# HalfBridge.net
KiCad netlist of a schematic drawn in Altium Designer
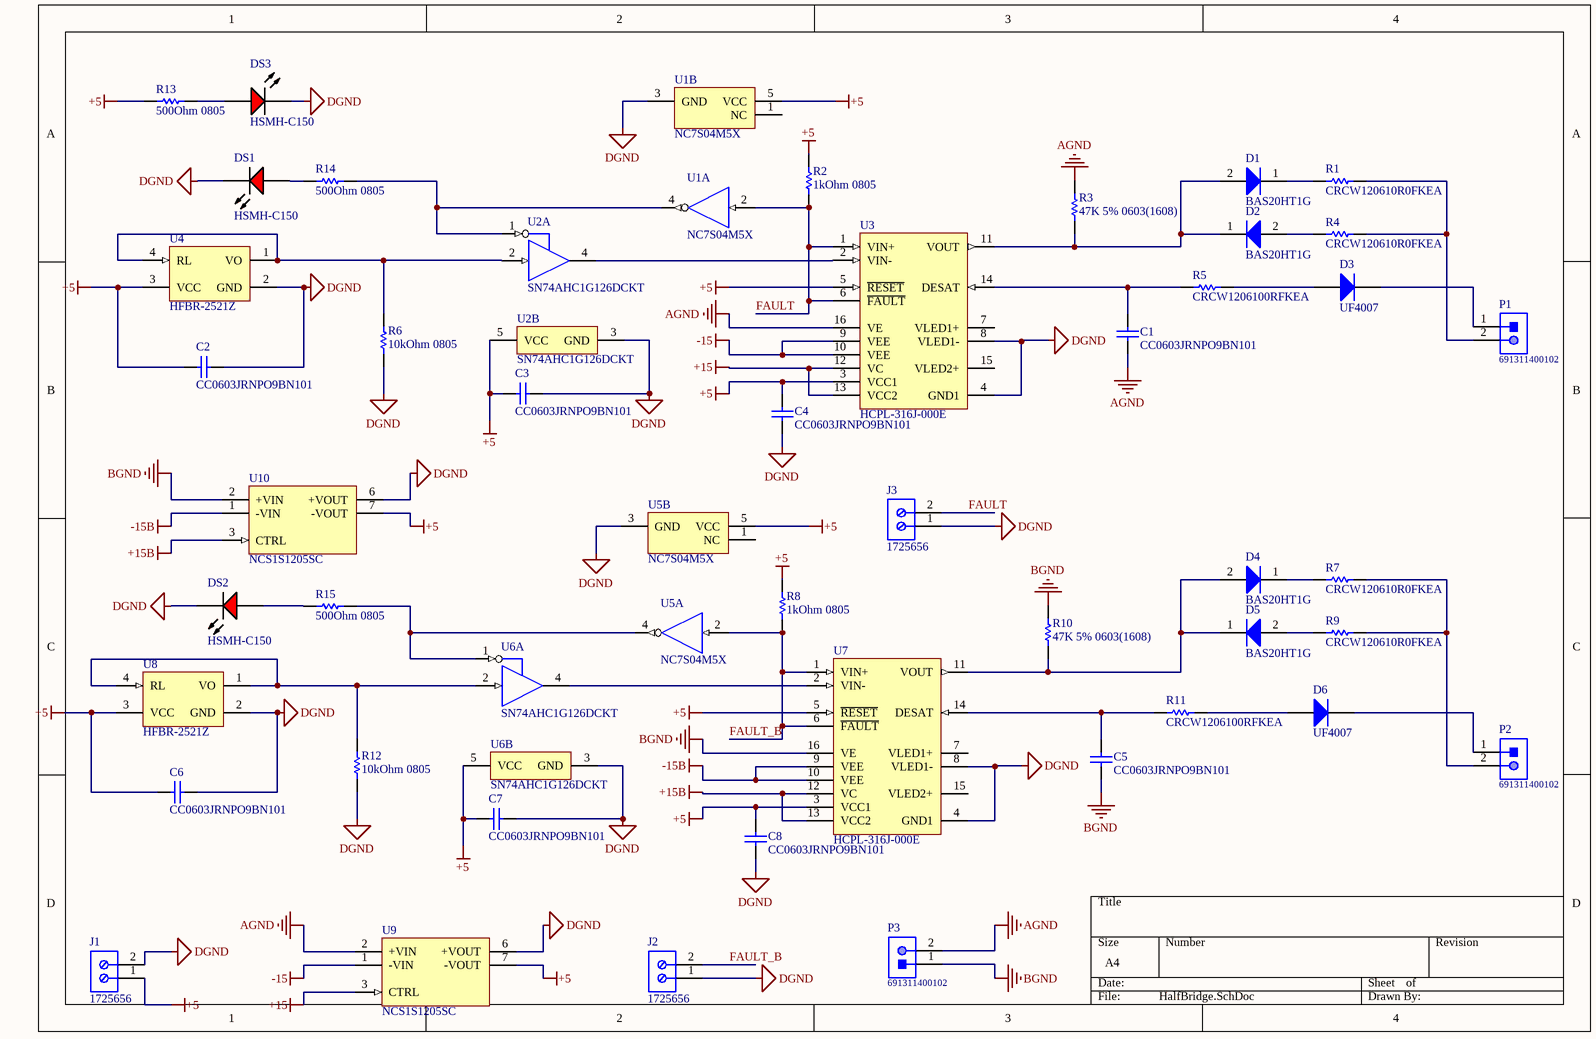
[diagram p0: HalfBridge.SchDoc]

(export (version "E")
  (design (tool "Eeschema 10.0.6"))
  (components
    (comp (ref "C1")
      (value "CC0603JRNPO9BN101")
      (footprint "CAPC1608X90X40ML10T20")
      (description "Chip Capacitor, 100 pF, +/- 5%, 50 V, -55 to 125 degC, 0603 (1608 Metric), RoHS, Tape and Reel")
      (fields (field (name "TOLERANCE") "5%") (field (name "VOLTAGE") "50V"))
      (libsource (lib "Altium Content Vault") (part "CAP-NP-2"))
    )
    (comp (ref "C2")
      (value "CC0603JRNPO9BN101")
      (footprint "CAPC1608X90X40ML10T20")
      (description "Chip Capacitor, 100 pF, +/- 5%, 50 V, -55 to 125 degC, 0603 (1608 Metric), RoHS, Tape and Reel")
      (fields (field (name "TOLERANCE") "5%") (field (name "VOLTAGE") "50V"))
      (libsource (lib "Altium Content Vault") (part "CAP-NP-2"))
    )
    (comp (ref "C3")
      (value "CC0603JRNPO9BN101")
      (footprint "CAPC1608X90X40ML10T20")
      (description "Chip Capacitor, 100 pF, +/- 5%, 50 V, -55 to 125 degC, 0603 (1608 Metric), RoHS, Tape and Reel")
      (fields (field (name "TOLERANCE") "5%") (field (name "VOLTAGE") "50V"))
      (libsource (lib "Altium Content Vault") (part "CAP-NP-2"))
    )
    (comp (ref "C4")
      (value "CC0603JRNPO9BN101")
      (footprint "CAPC1608X90X40ML10T20")
      (description "Chip Capacitor, 100 pF, +/- 5%, 50 V, -55 to 125 degC, 0603 (1608 Metric), RoHS, Tape and Reel")
      (fields (field (name "TOLERANCE") "5%") (field (name "VOLTAGE") "50V"))
      (libsource (lib "Altium Content Vault") (part "CAP-NP-2"))
    )
    (comp (ref "C5")
      (value "CC0603JRNPO9BN101")
      (footprint "CAPC1608X90X40ML10T20")
      (description "Chip Capacitor, 100 pF, +/- 5%, 50 V, -55 to 125 degC, 0603 (1608 Metric), RoHS, Tape and Reel")
      (fields (field (name "TOLERANCE") "5%") (field (name "VOLTAGE") "50V"))
      (libsource (lib "Altium Content Vault") (part "CAP-NP-2"))
    )
    (comp (ref "C6")
      (value "CC0603JRNPO9BN101")
      (footprint "CAPC1608X90X40ML10T20")
      (description "Chip Capacitor, 100 pF, +/- 5%, 50 V, -55 to 125 degC, 0603 (1608 Metric), RoHS, Tape and Reel")
      (fields (field (name "TOLERANCE") "5%") (field (name "VOLTAGE") "50V"))
      (libsource (lib "Altium Content Vault") (part "CAP-NP-2"))
    )
    (comp (ref "C7")
      (value "CC0603JRNPO9BN101")
      (footprint "CAPC1608X90X40ML10T20")
      (description "Chip Capacitor, 100 pF, +/- 5%, 50 V, -55 to 125 degC, 0603 (1608 Metric), RoHS, Tape and Reel")
      (fields (field (name "TOLERANCE") "5%") (field (name "VOLTAGE") "50V"))
      (libsource (lib "Altium Content Vault") (part "CAP-NP-2"))
    )
    (comp (ref "C8")
      (value "CC0603JRNPO9BN101")
      (footprint "CAPC1608X90X40ML10T20")
      (description "Chip Capacitor, 100 pF, +/- 5%, 50 V, -55 to 125 degC, 0603 (1608 Metric), RoHS, Tape and Reel")
      (fields (field (name "TOLERANCE") "5%") (field (name "VOLTAGE") "50V"))
      (libsource (lib "Altium Content Vault") (part "CAP-NP-2"))
    )
    (comp (ref "D1")
      (value "BAS20HT1G")
      (footprint "ONSC-SOD-323-2-477-02_V")
      (description "High Voltage Switching Diode, 2-Pin SOD-323, Pb-Free, Tape and Reel")
      (fields (field (name "MANUFACTURER") "On Semiconductor"))
      (libsource (lib "Altium Content Vault") (part "ONSC-D-K1A2-2"))
    )
    (comp (ref "D2")
      (value "BAS20HT1G")
      (footprint "ONSC-SOD-323-2-477-02_V")
      (description "High Voltage Switching Diode, 2-Pin SOD-323, Pb-Free, Tape and Reel")
      (fields (field (name "MANUFACTURER") "On Semiconductor"))
      (libsource (lib "Altium Content Vault") (part "ONSC-D-K1A2-2"))
    )
    (comp (ref "D3")
      (value "UF4007")
      (footprint "FAIR-DO-41-2")
      (description "Fast Rectufuer, 2.08 W, 2-Pin DO-41, RoHS, Tape and Reel")
      (fields (field (name "MANUFACTURER") "Fairchild"))
      (libsource (lib "Altium Content Vault") (part "D-AK-2"))
    )
    (comp (ref "D4")
      (value "BAS20HT1G")
      (footprint "ONSC-SOD-323-2-477-02_V")
      (description "High Voltage Switching Diode, 2-Pin SOD-323, Pb-Free, Tape and Reel")
      (fields (field (name "MANUFACTURER") "On Semiconductor"))
      (libsource (lib "Altium Content Vault") (part "ONSC-D-K1A2-2"))
    )
    (comp (ref "D5")
      (value "BAS20HT1G")
      (footprint "ONSC-SOD-323-2-477-02_V")
      (description "High Voltage Switching Diode, 2-Pin SOD-323, Pb-Free, Tape and Reel")
      (fields (field (name "MANUFACTURER") "On Semiconductor"))
      (libsource (lib "Altium Content Vault") (part "ONSC-D-K1A2-2"))
    )
    (comp (ref "D6")
      (value "UF4007")
      (footprint "FAIR-DO-41-2")
      (description "Fast Rectufuer, 2.08 W, 2-Pin DO-41, RoHS, Tape and Reel")
      (fields (field (name "MANUFACTURER") "Fairchild"))
      (libsource (lib "Altium Content Vault") (part "D-AK-2"))
    )
    (comp (ref "DS1")
      (value "HSMH-C150")
      (footprint "AVAG-HSMX-C150_V")
      (description "LED Uni-Color Red, 65 mW, 25 mA, -40 to 85 degC, 2-Pin SMD, RoHS, Tape and Reel")
      (fields (field (name "MANUFACTURER") "Avago"))
      (libsource (lib "Altium Content Vault") (part "LED-RED-AK-2"))
    )
    (comp (ref "DS2")
      (value "HSMH-C150")
      (footprint "AVAG-HSMX-C150_V")
      (description "LED Uni-Color Red, 65 mW, 25 mA, -40 to 85 degC, 2-Pin SMD, RoHS, Tape and Reel")
      (fields (field (name "MANUFACTURER") "Avago"))
      (libsource (lib "Altium Content Vault") (part "LED-RED-AK-2"))
    )
    (comp (ref "DS3")
      (value "HSMH-C150")
      (footprint "AVAG-HSMX-C150_V")
      (description "LED Uni-Color Red, 65 mW, 25 mA, -40 to 85 degC, 2-Pin SMD, RoHS, Tape and Reel")
      (fields (field (name "MANUFACTURER") "Avago"))
      (libsource (lib "Altium Content Vault") (part "LED-RED-AK-2"))
    )
    (comp (ref "J1")
      (value "1725656")
      (footprint "PHOE-1725656-2")
      (description "Male Header, Pitch 2.54 mm, 1 x 2 Position, Height 9 mm, Tail Length 3.5 mm")
      (fields (field (name "MANUFACTURER") "Phoenix Contact"))
      (libsource (lib "Altium Content Vault") (part "CN-1P-F-TB2"))
    )
    (comp (ref "J2")
      (value "1725656")
      (footprint "PHOE-1725656-2")
      (description "Male Header, Pitch 2.54 mm, 1 x 2 Position, Height 9 mm, Tail Length 3.5 mm")
      (fields (field (name "MANUFACTURER") "Phoenix Contact"))
      (libsource (lib "Altium Content Vault") (part "CN-1P-F-TB2"))
    )
    (comp (ref "J3")
      (value "1725656")
      (footprint "PHOE-1725656-2")
      (description "Male Header, Pitch 2.54 mm, 1 x 2 Position, Height 9 mm, Tail Length 3.5 mm")
      (fields (field (name "MANUFACTURER") "Phoenix Contact"))
      (libsource (lib "Altium Content Vault") (part "CN-1P-F-TB2"))
    )
    (comp (ref "P1")
      (value "691311400102")
      (footprint "691311400102")
      (description "Serie 3114 - 7.62mm Close Vertical PCB Header WR-TBL, 2 pin")
      (fields (field (name "MANUFACTURER") "Wurth Elektronik") (field (name "PUBLISHER") "WurthElektronik"))
      (libsource (lib "Altium Content Vault") (part "WE-CN-1P-M-R2"))
    )
    (comp (ref "P2")
      (value "691311400102")
      (footprint "691311400102")
      (description "Serie 3114 - 7.62mm Close Vertical PCB Header WR-TBL, 2 pin")
      (fields (field (name "MANUFACTURER") "Wurth Elektronik") (field (name "PUBLISHER") "WurthElektronik"))
      (libsource (lib "Altium Content Vault") (part "WE-CN-1P-M-R2"))
    )
    (comp (ref "P3")
      (value "691311400102")
      (footprint "691311400102")
      (description "Serie 3114 - 7.62mm Close Vertical PCB Header WR-TBL, 2 pin")
      (fields (field (name "MANUFACTURER") "Wurth Elektronik") (field (name "PUBLISHER") "WurthElektronik"))
      (libsource (lib "") (part "WE-CN-1P-M-R2_1"))
    )
    (comp (ref "R1")
      (value "CRCW120610R0FKEA")
      (footprint "RESC3216X60X45ML10T20")
      (fields (field (name "MANUFACTURER") "Vishay Dale"))
      (libsource (lib "Altium Content Vault") (part "RES"))
    )
    (comp (ref "R2")
      (value "1kOhm 0805")
      (footprint "RESC2013X50X30LL20T20")
      (fields (field (name "MANUFACTURER") "Vishay Dale") (field (name "PART NUMBER") "CRCW08050000Z0EA"))
      (libsource (lib "Altium Content Vault") (part "RES"))
    )
    (comp (ref "R3")
      (value "47K 5% 0603(1608)")
      (footprint "RESC0603(1608)_L")
      (description "47K 0.1W 5% 0603 (1608 Metric)  SMD")
      (fields (field (name "TOLERANCE") "5 %") (field (name "POWER") "0.1 W"))
      (libsource (lib "Altium Content Vault") (part "RES"))
    )
    (comp (ref "R4")
      (value "CRCW120610R0FKEA")
      (footprint "RESC3216X60X45ML10T20")
      (fields (field (name "MANUFACTURER") "Vishay Dale"))
      (libsource (lib "Altium Content Vault") (part "RES"))
    )
    (comp (ref "R5")
      (value "CRCW1206100RFKEA")
      (footprint "RESC3216X60X45ML10T20")
      (fields (field (name "MANUFACTURER") "Vishay Dale"))
      (libsource (lib "Altium Content Vault") (part "RES"))
    )
    (comp (ref "R6")
      (value "10kOhm 0805")
      (footprint "RESC2013X50X30LL20T20")
      (fields (field (name "MANUFACTURER") "Vishay Dale") (field (name "PART NUMBER") "CRCW08050000Z0EA"))
      (libsource (lib "Altium Content Vault") (part "RES"))
    )
    (comp (ref "R7")
      (value "CRCW120610R0FKEA")
      (footprint "RESC3216X60X45ML10T20")
      (fields (field (name "MANUFACTURER") "Vishay Dale"))
      (libsource (lib "Altium Content Vault") (part "RES"))
    )
    (comp (ref "R8")
      (value "1kOhm 0805")
      (footprint "RESC2013X50X30LL20T20")
      (fields (field (name "MANUFACTURER") "Vishay Dale") (field (name "PART NUMBER") "CRCW08050000Z0EA"))
      (libsource (lib "Altium Content Vault") (part "RES"))
    )
    (comp (ref "R9")
      (value "CRCW120610R0FKEA")
      (footprint "RESC3216X60X45ML10T20")
      (fields (field (name "MANUFACTURER") "Vishay Dale"))
      (libsource (lib "Altium Content Vault") (part "RES"))
    )
    (comp (ref "R10")
      (value "47K 5% 0603(1608)")
      (footprint "RESC0603(1608)_L")
      (description "47K 0.1W 5% 0603 (1608 Metric)  SMD")
      (fields (field (name "TOLERANCE") "5 %") (field (name "POWER") "0.1 W"))
      (libsource (lib "Altium Content Vault") (part "RES"))
    )
    (comp (ref "R11")
      (value "CRCW1206100RFKEA")
      (footprint "RESC3216X60X45ML10T20")
      (fields (field (name "MANUFACTURER") "Vishay Dale"))
      (libsource (lib "Altium Content Vault") (part "RES"))
    )
    (comp (ref "R12")
      (value "10kOhm 0805")
      (footprint "RESC2013X50X30LL20T20")
      (fields (field (name "MANUFACTURER") "Vishay Dale") (field (name "PART NUMBER") "CRCW08050000Z0EA"))
      (libsource (lib "Altium Content Vault") (part "RES"))
    )
    (comp (ref "R13")
      (value "500Ohm 0805")
      (footprint "RESC2013X50X30LL20T20")
      (fields (field (name "MANUFACTURER") "Vishay Dale") (field (name "PART NUMBER") "CRCW08050000Z0EA"))
      (libsource (lib "Altium Content Vault") (part "RES"))
    )
    (comp (ref "R14")
      (value "500Ohm 0805")
      (footprint "RESC2013X50X30LL20T20")
      (fields (field (name "MANUFACTURER") "Vishay Dale") (field (name "PART NUMBER") "CRCW08050000Z0EA"))
      (libsource (lib "Altium Content Vault") (part "RES"))
    )
    (comp (ref "R15")
      (value "500Ohm 0805")
      (footprint "RESC2013X50X30LL20T20")
      (fields (field (name "MANUFACTURER") "Vishay Dale") (field (name "PART NUMBER") "CRCW08050000Z0EA"))
      (libsource (lib "Altium Content Vault") (part "RES"))
    )
    (comp (ref "U1")
      (value "NC7S04M5X")
      (footprint "FAIR-SOT23-5_V")
      (description "TinyLogic(R) HS Inverter, 2.6 mA, 2 to 6 V, -40 to 85 degC, 5-Pin SOT23, RoHS, Tape and Reel")
      (fields (field (name "MANUFACTURER") "Fairchild Semiconductor"))
      (libsource (lib "Altium Content Vault") (part "FAIR-NC7SX04-5"))
    )
    (comp (ref "U2")
      (value "SN74AHC1G126DCKT")
      (footprint "DCK0005A_N")
      (description "Single Bus Buffer Gate With 3-State Outputs, DCK0005A, SMALL T&R")
      (fields
        (field (name "MANUFACTURER") "Texas Instruments")
        (field (name "GENERIC PART NUMBER") "SN74AHC1G126")
      )
      (libsource (lib "Altium Content Vault") (part "TI-SN74XXXXXX126-5"))
    )
    (comp (ref "U3")
      (value "HCPL-316J-000E")
      (footprint "AVAG-SOIC-16_V")
      (fields (field (name "MANUFACTURER") "AvagoTechnologies"))
      (libsource (lib "Altium Content Vault") (part "AVAG-HCPL-316J-SOIC-16"))
    )
    (comp (ref "U4")
      (value "HFBR-2521Z")
      (footprint "BCM-HFBR-2521Z-4")
      (description "The Versatile Fiber Optic Connection, 5 MBd, -40 to 85 degC, 4-Pin, RoHS, Rail/Tube")
      (fields (field (name "MANUFACTURER") "Broadcom"))
      (libsource (lib "Altium Content Vault") (part "BCM-HFBR-2521Z-4"))
    )
    (comp (ref "U5")
      (value "NC7S04M5X")
      (footprint "FAIR-SOT23-5_V")
      (description "TinyLogic(R) HS Inverter, 2.6 mA, 2 to 6 V, -40 to 85 degC, 5-Pin SOT23, RoHS, Tape and Reel")
      (fields (field (name "MANUFACTURER") "Fairchild Semiconductor"))
      (libsource (lib "Altium Content Vault") (part "FAIR-NC7SX04-5"))
    )
    (comp (ref "U6")
      (value "SN74AHC1G126DCKT")
      (footprint "DCK0005A_N")
      (description "Single Bus Buffer Gate With 3-State Outputs, DCK0005A, SMALL T&R")
      (fields
        (field (name "MANUFACTURER") "Texas Instruments")
        (field (name "GENERIC PART NUMBER") "SN74AHC1G126")
      )
      (libsource (lib "Altium Content Vault") (part "TI-SN74XXXXXX126-5"))
    )
    (comp (ref "U7")
      (value "HCPL-316J-000E")
      (footprint "AVAG-SOIC-16_V")
      (fields (field (name "MANUFACTURER") "AvagoTechnologies"))
      (libsource (lib "Altium Content Vault") (part "AVAG-HCPL-316J-SOIC-16"))
    )
    (comp (ref "U8")
      (value "HFBR-2521Z")
      (footprint "BCM-HFBR-2521Z-4")
      (description "The Versatile Fiber Optic Connection, 5 MBd, -40 to 85 degC, 4-Pin, RoHS, Rail/Tube")
      (fields (field (name "MANUFACTURER") "Broadcom"))
      (libsource (lib "Altium Content Vault") (part "BCM-HFBR-2521Z-4"))
    )
    (comp (ref "U9")
      (value "NCS1S1205SC")
      (footprint "MURA-NCS1S1205SC-5_V")
      (fields (field (name "GENERIC PART NUMBER") "NCS1"))
      (libsource (lib "Altium Content Vault") (part "MURA-NCS1S1205SC-5"))
    )
    (comp (ref "U10")
      (value "NCS1S1205SC")
      (footprint "MURA-NCS1S1205SC-5_V")
      (fields (field (name "GENERIC PART NUMBER") "NCS1"))
      (libsource (lib "Altium Content Vault") (part "MURA-NCS1S1205SC-5"))
    )
  )
  (nets
    (net (code "1") (name "+5") (class "Default")
      (node (ref "C2") (pin "1") (pinfunction "1_1") (pintype "passive"))
      (node (ref "C3") (pin "1") (pinfunction "1_1") (pintype "passive"))
      (node (ref "C4") (pin "1") (pinfunction "1_1") (pintype "passive"))
      (node (ref "C6") (pin "1") (pinfunction "1_1") (pintype "passive"))
      (node (ref "C7") (pin "1") (pinfunction "1_1") (pintype "passive"))
      (node (ref "C8") (pin "1") (pinfunction "1_1") (pintype "passive"))
      (node (ref "J1") (pin "1") (pinfunction "1_1") (pintype "passive"))
      (node (ref "R13") (pin "2") (pinfunction "2_2") (pintype "passive"))
      (node (ref "R2") (pin "2") (pinfunction "2_2") (pintype "passive"))
      (node (ref "R8") (pin "2") (pinfunction "2_2") (pintype "passive"))
      (node (ref "U1") (pin "5") (pinfunction "VCC_5") (pintype "power_in"))
      (node (ref "U10") (pin "7") (pinfunction "-VOUT_7") (pintype "power_in"))
      (node (ref "U2") (pin "5") (pinfunction "VCC_5") (pintype "power_in"))
      (node (ref "U3") (pin "3") (pinfunction "VCC1_3") (pintype "power_in"))
      (node (ref "U3") (pin "5") (pinfunction "~{RESET}_5") (pintype "input"))
      (node (ref "U4") (pin "3") (pinfunction "VCC_3") (pintype "power_in"))
      (node (ref "U5") (pin "5") (pinfunction "VCC_5") (pintype "power_in"))
      (node (ref "U6") (pin "5") (pinfunction "VCC_5") (pintype "power_in"))
      (node (ref "U7") (pin "3") (pinfunction "VCC1_3") (pintype "power_in"))
      (node (ref "U7") (pin "5") (pinfunction "~{RESET}_5") (pintype "input"))
      (node (ref "U8") (pin "3") (pinfunction "VCC_3") (pintype "power_in"))
      (node (ref "U9") (pin "7") (pinfunction "-VOUT_7") (pintype "power_in"))
    )
    (net (code "2") (name "+15") (class "Default")
      (node (ref "U3") (pin "12") (pinfunction "VC_12") (pintype "power_in"))
      (node (ref "U3") (pin "13") (pinfunction "VCC2_13") (pintype "power_in"))
      (node (ref "U9") (pin "3") (pinfunction "CTRL_3") (pintype "input"))
    )
    (net (code "3") (name "+15B") (class "Default")
      (node (ref "U10") (pin "3") (pinfunction "CTRL_3") (pintype "input"))
      (node (ref "U7") (pin "12") (pinfunction "VC_12") (pintype "power_in"))
      (node (ref "U7") (pin "13") (pinfunction "VCC2_13") (pintype "power_in"))
    )
    (net (code "4") (name "-15") (class "Default")
      (node (ref "U3") (pin "10") (pinfunction "VEE_10") (pintype "power_in"))
      (node (ref "U3") (pin "9") (pinfunction "VEE_9") (pintype "power_in"))
      (node (ref "U9") (pin "1") (pinfunction "-VIN_1") (pintype "power_in"))
    )
    (net (code "5") (name "-15B") (class "Default")
      (node (ref "U10") (pin "1") (pinfunction "-VIN_1") (pintype "power_in"))
      (node (ref "U7") (pin "10") (pinfunction "VEE_10") (pintype "power_in"))
      (node (ref "U7") (pin "9") (pinfunction "VEE_9") (pintype "power_in"))
    )
    (net (code "6") (name "/FAULT") (class "Default")
      (node (ref "J3") (pin "2") (pinfunction "2_2") (pintype "passive"))
      (node (ref "R2") (pin "1") (pinfunction "1_1") (pintype "passive"))
      (node (ref "U1") (pin "2") (pinfunction "A_2") (pintype "input"))
      (node (ref "U3") (pin "1") (pinfunction "VIN+_1") (pintype "input"))
      (node (ref "U3") (pin "6") (pinfunction "~{FAULT}_6") (pintype "tri_state"))
    )
    (net (code "7") (name "/FAULT_B") (class "Default")
      (node (ref "J2") (pin "2") (pinfunction "2_2") (pintype "passive"))
      (node (ref "R8") (pin "1") (pinfunction "1_1") (pintype "passive"))
      (node (ref "U5") (pin "2") (pinfunction "A_2") (pintype "input"))
      (node (ref "U7") (pin "1") (pinfunction "VIN+_1") (pintype "input"))
      (node (ref "U7") (pin "6") (pinfunction "~{FAULT}_6") (pintype "tri_state"))
    )
    (net (code "8") (name "AGND") (class "Default")
      (node (ref "C1") (pin "2") (pinfunction "2_2") (pintype "passive"))
      (node (ref "P3") (pin "2") (pinfunction "2_2") (pintype "passive"))
      (node (ref "R3") (pin "2") (pinfunction "2_2") (pintype "passive"))
      (node (ref "U3") (pin "16") (pinfunction "VE_16") (pintype "power_in"))
      (node (ref "U9") (pin "2") (pinfunction "+VIN_2") (pintype "power_in"))
    )
    (net (code "9") (name "BGND") (class "Default")
      (node (ref "C5") (pin "2") (pinfunction "2_2") (pintype "passive"))
      (node (ref "P3") (pin "1") (pinfunction "1_1") (pintype "passive"))
      (node (ref "R10") (pin "2") (pinfunction "2_2") (pintype "passive"))
      (node (ref "U10") (pin "2") (pinfunction "+VIN_2") (pintype "power_in"))
      (node (ref "U7") (pin "16") (pinfunction "VE_16") (pintype "power_in"))
    )
    (net (code "10") (name "DGND") (class "Default")
      (node (ref "C2") (pin "2") (pinfunction "2_2") (pintype "passive"))
      (node (ref "C3") (pin "2") (pinfunction "2_2") (pintype "passive"))
      (node (ref "C4") (pin "2") (pinfunction "2_2") (pintype "passive"))
      (node (ref "C6") (pin "2") (pinfunction "2_2") (pintype "passive"))
      (node (ref "C7") (pin "2") (pinfunction "2_2") (pintype "passive"))
      (node (ref "C8") (pin "2") (pinfunction "2_2") (pintype "passive"))
      (node (ref "DS1") (pin "2") (pinfunction "K_2") (pintype "passive"))
      (node (ref "DS2") (pin "2") (pinfunction "K_2") (pintype "passive"))
      (node (ref "DS3") (pin "2") (pinfunction "K_2") (pintype "passive"))
      (node (ref "J1") (pin "2") (pinfunction "2_2") (pintype "passive"))
      (node (ref "J2") (pin "1") (pinfunction "1_1") (pintype "passive"))
      (node (ref "J3") (pin "1") (pinfunction "1_1") (pintype "passive"))
      (node (ref "R12") (pin "1") (pinfunction "1_1") (pintype "passive"))
      (node (ref "R6") (pin "1") (pinfunction "1_1") (pintype "passive"))
      (node (ref "U1") (pin "3") (pinfunction "GND_3") (pintype "power_in"))
      (node (ref "U10") (pin "6") (pinfunction "+VOUT_6") (pintype "power_in"))
      (node (ref "U2") (pin "3") (pinfunction "GND_3") (pintype "power_in"))
      (node (ref "U3") (pin "4") (pinfunction "GND1_4") (pintype "power_in"))
      (node (ref "U3") (pin "8") (pinfunction "VLED1-_8") (pintype "passive"))
      (node (ref "U4") (pin "2") (pinfunction "GND_2") (pintype "power_in"))
      (node (ref "U5") (pin "3") (pinfunction "GND_3") (pintype "power_in"))
      (node (ref "U6") (pin "3") (pinfunction "GND_3") (pintype "power_in"))
      (node (ref "U7") (pin "4") (pinfunction "GND1_4") (pintype "power_in"))
      (node (ref "U7") (pin "8") (pinfunction "VLED1-_8") (pintype "passive"))
      (node (ref "U8") (pin "2") (pinfunction "GND_2") (pintype "power_in"))
      (node (ref "U9") (pin "6") (pinfunction "+VOUT_6") (pintype "power_in"))
    )
    (net (code "11") (name "Net-(D1-A)") (class "Default")
      (node (ref "D1") (pin "2") (pinfunction "A_2") (pintype "passive"))
      (node (ref "D2") (pin "1") (pinfunction "K_1") (pintype "passive"))
      (node (ref "R3") (pin "1") (pinfunction "1_1") (pintype "passive"))
      (node (ref "U3") (pin "11") (pinfunction "VOUT_11") (pintype "output"))
    )
    (net (code "12") (name "Net-(D1-K)") (class "Default")
      (node (ref "D1") (pin "1") (pinfunction "K_1") (pintype "passive"))
      (node (ref "R1") (pin "1") (pinfunction "1_1") (pintype "passive"))
    )
    (net (code "13") (name "Net-(D2-A)") (class "Default")
      (node (ref "D2") (pin "2") (pinfunction "A_2") (pintype "passive"))
      (node (ref "R4") (pin "1") (pinfunction "1_1") (pintype "passive"))
    )
    (net (code "14") (name "Net-(D3-A)") (class "Default")
      (node (ref "D3") (pin "1") (pinfunction "A_1") (pintype "passive"))
      (node (ref "R5") (pin "2") (pinfunction "2_2") (pintype "passive"))
    )
    (net (code "15") (name "Net-(D3-K)") (class "Default")
      (node (ref "D3") (pin "2") (pinfunction "K_2") (pintype "passive"))
      (node (ref "P1") (pin "1") (pinfunction "1_1") (pintype "passive"))
    )
    (net (code "16") (name "Net-(D4-A)") (class "Default")
      (node (ref "D4") (pin "2") (pinfunction "A_2") (pintype "passive"))
      (node (ref "D5") (pin "1") (pinfunction "K_1") (pintype "passive"))
      (node (ref "R10") (pin "1") (pinfunction "1_1") (pintype "passive"))
      (node (ref "U7") (pin "11") (pinfunction "VOUT_11") (pintype "output"))
    )
    (net (code "17") (name "Net-(D4-K)") (class "Default")
      (node (ref "D4") (pin "1") (pinfunction "K_1") (pintype "passive"))
      (node (ref "R7") (pin "1") (pinfunction "1_1") (pintype "passive"))
    )
    (net (code "18") (name "Net-(D5-A)") (class "Default")
      (node (ref "D5") (pin "2") (pinfunction "A_2") (pintype "passive"))
      (node (ref "R9") (pin "1") (pinfunction "1_1") (pintype "passive"))
    )
    (net (code "19") (name "Net-(D6-A)") (class "Default")
      (node (ref "D6") (pin "1") (pinfunction "A_1") (pintype "passive"))
      (node (ref "R11") (pin "2") (pinfunction "2_2") (pintype "passive"))
    )
    (net (code "20") (name "Net-(D6-K)") (class "Default")
      (node (ref "D6") (pin "2") (pinfunction "K_2") (pintype "passive"))
      (node (ref "P2") (pin "1") (pinfunction "1_1") (pintype "passive"))
    )
    (net (code "21") (name "Net-(DS1-A)") (class "Default")
      (node (ref "DS1") (pin "1") (pinfunction "A_1") (pintype "passive"))
      (node (ref "R14") (pin "2") (pinfunction "2_2") (pintype "passive"))
    )
    (net (code "22") (name "Net-(DS2-A)") (class "Default")
      (node (ref "DS2") (pin "1") (pinfunction "A_1") (pintype "passive"))
      (node (ref "R15") (pin "2") (pinfunction "2_2") (pintype "passive"))
    )
    (net (code "23") (name "Net-(DS3-A)") (class "Default")
      (node (ref "DS3") (pin "1") (pinfunction "A_1") (pintype "passive"))
      (node (ref "R13") (pin "1") (pinfunction "1_1") (pintype "passive"))
    )
    (net (code "24") (name "Net-(P1-Pad2)") (class "Default")
      (node (ref "P1") (pin "2") (pinfunction "2_2") (pintype "passive"))
      (node (ref "R1") (pin "2") (pinfunction "2_2") (pintype "passive"))
      (node (ref "R4") (pin "2") (pinfunction "2_2") (pintype "passive"))
    )
    (net (code "25") (name "Net-(P2-Pad2)") (class "Default")
      (node (ref "P2") (pin "2") (pinfunction "2_2") (pintype "passive"))
      (node (ref "R7") (pin "2") (pinfunction "2_2") (pintype "passive"))
      (node (ref "R9") (pin "2") (pinfunction "2_2") (pintype "passive"))
    )
    (net (code "26") (name "Net-(U1A-Y)") (class "Default")
      (node (ref "R14") (pin "1") (pinfunction "1_1") (pintype "passive"))
      (node (ref "U1") (pin "4") (pinfunction "Y_4") (pintype "output"))
      (node (ref "U2") (pin "1") (pinfunction "OE_1") (pintype "input"))
    )
    (net (code "27") (name "Net-(U2A-A)") (class "Default")
      (node (ref "R6") (pin "2") (pinfunction "2_2") (pintype "passive"))
      (node (ref "U2") (pin "2") (pinfunction "A_2") (pintype "input"))
      (node (ref "U4") (pin "1") (pinfunction "VO_1") (pintype "power_in"))
      (node (ref "U4") (pin "4") (pinfunction "RL_4") (pintype "input"))
    )
    (net (code "28") (name "Net-(U2A-Y)") (class "Default")
      (node (ref "U2") (pin "4") (pinfunction "Y_4") (pintype "tri_state"))
      (node (ref "U3") (pin "2") (pinfunction "VIN-_2") (pintype "input"))
    )
    (net (code "29") (name "Net-(U3-DESAT)") (class "Default")
      (node (ref "C1") (pin "1") (pinfunction "1_1") (pintype "passive"))
      (node (ref "R5") (pin "1") (pinfunction "1_1") (pintype "passive"))
      (node (ref "U3") (pin "14") (pinfunction "DESAT_14") (pintype "input"))
    )
    (net (code "30") (name "Net-(U5A-Y)") (class "Default")
      (node (ref "R15") (pin "1") (pinfunction "1_1") (pintype "passive"))
      (node (ref "U5") (pin "4") (pinfunction "Y_4") (pintype "output"))
      (node (ref "U6") (pin "1") (pinfunction "OE_1") (pintype "input"))
    )
    (net (code "31") (name "Net-(U6A-A)") (class "Default")
      (node (ref "R12") (pin "2") (pinfunction "2_2") (pintype "passive"))
      (node (ref "U6") (pin "2") (pinfunction "A_2") (pintype "input"))
      (node (ref "U8") (pin "1") (pinfunction "VO_1") (pintype "power_in"))
      (node (ref "U8") (pin "4") (pinfunction "RL_4") (pintype "input"))
    )
    (net (code "32") (name "Net-(U6A-Y)") (class "Default")
      (node (ref "U6") (pin "4") (pinfunction "Y_4") (pintype "tri_state"))
      (node (ref "U7") (pin "2") (pinfunction "VIN-_2") (pintype "input"))
    )
    (net (code "33") (name "Net-(U7-DESAT)") (class "Default")
      (node (ref "C5") (pin "1") (pinfunction "1_1") (pintype "passive"))
      (node (ref "R11") (pin "1") (pinfunction "1_1") (pintype "passive"))
      (node (ref "U7") (pin "14") (pinfunction "DESAT_14") (pintype "input"))
    )
    (net (code "34") (name "unconnected-(U1B-NC-Pad1)") (class "Default")
      (node (ref "U1") (pin "1") (pinfunction "NC_1") (pintype "power_in"))
    )
    (net (code "35") (name "unconnected-(U3-VLED1+-Pad7)") (class "Default")
      (node (ref "U3") (pin "7") (pinfunction "VLED1+_7") (pintype "passive"))
    )
    (net (code "36") (name "unconnected-(U3-VLED2+-Pad15)") (class "Default")
      (node (ref "U3") (pin "15") (pinfunction "VLED2+_15") (pintype "passive"))
    )
    (net (code "37") (name "unconnected-(U5B-NC-Pad1)") (class "Default")
      (node (ref "U5") (pin "1") (pinfunction "NC_1") (pintype "power_in"))
    )
    (net (code "38") (name "unconnected-(U7-VLED1+-Pad7)") (class "Default")
      (node (ref "U7") (pin "7") (pinfunction "VLED1+_7") (pintype "passive"))
    )
    (net (code "39") (name "unconnected-(U7-VLED2+-Pad15)") (class "Default")
      (node (ref "U7") (pin "15") (pinfunction "VLED2+_15") (pintype "passive"))
    )
  )
)
